# NODE_MCU_EXTEND_Project.net
KiCad netlist of a schematic drawn in Altium Designer
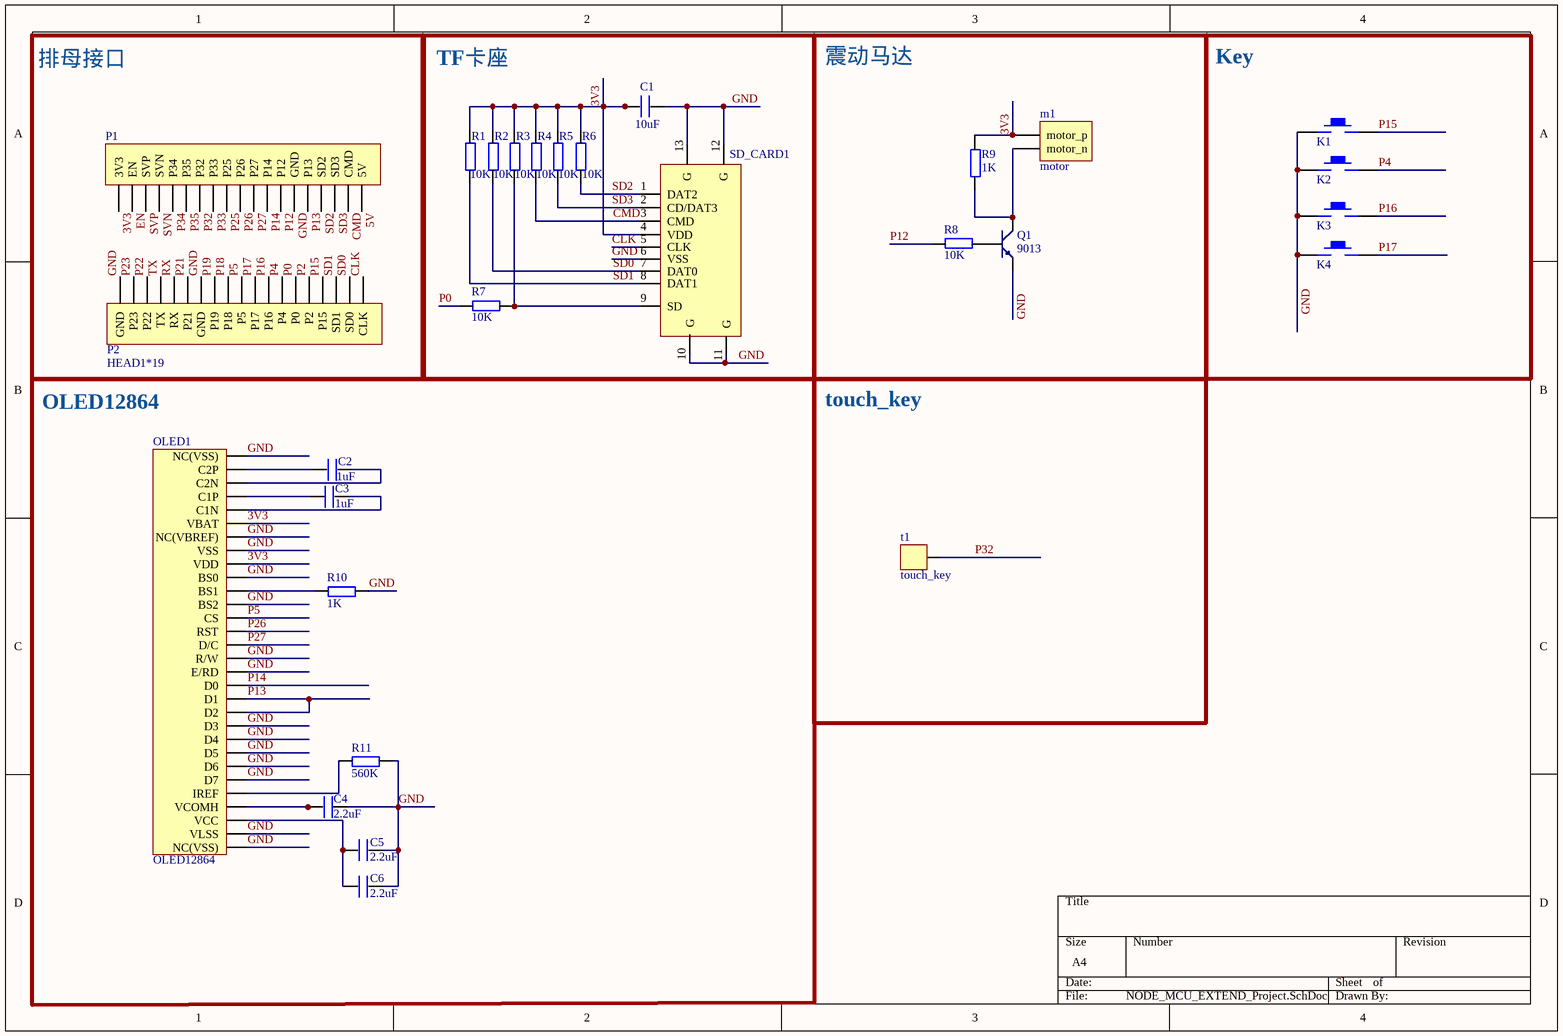
[diagram p0: NODE_MCU_EXTEND_Project.SchDoc]

(export (version "E")
  (design (tool "Eeschema 10.0.6"))
  (components
    (comp (ref "C1")
      (value "10uF")
      (footprint "0603P - duplicate")
      (libsource (lib "altium-import") (part "root_0_C_"))
    )
    (comp (ref "C2")
      (value "1uF")
      (footprint "0603P - duplicate")
      (libsource (lib "altium-import") (part "root_0_C_"))
    )
    (comp (ref "C3")
      (value "1uF")
      (footprint "0603P - duplicate")
      (libsource (lib "altium-import") (part "root_0_C_"))
    )
    (comp (ref "C4")
      (value "2.2uF")
      (footprint "0603P - duplicate")
      (libsource (lib "altium-import") (part "root_0_C_"))
    )
    (comp (ref "C5")
      (value "2.2uF")
      (footprint "0603P - duplicate")
      (libsource (lib "altium-import") (part "root_0_C_"))
    )
    (comp (ref "C6")
      (value "2.2uF")
      (footprint "0603P - duplicate")
      (libsource (lib "altium-import") (part "root_0_C_"))
    )
    (comp (ref "K1")
      (value "KEY_M")
      (footprint "KEY")
      (libsource (lib "NODE_MCU_EXTEND_Project") (part "KEY_M"))
    )
    (comp (ref "K2")
      (value "KEY_M")
      (footprint "KEY")
      (libsource (lib "NODE_MCU_EXTEND_Project") (part "KEY_M"))
    )
    (comp (ref "K3")
      (value "KEY_M")
      (footprint "KEY")
      (libsource (lib "NODE_MCU_EXTEND_Project") (part "KEY_M"))
    )
    (comp (ref "K4")
      (value "KEY_M")
      (footprint "KEY")
      (libsource (lib "NODE_MCU_EXTEND_Project") (part "KEY_M"))
    )
    (comp (ref "m1")
      (value "motor")
      (footprint "motor")
      (fields (field (name "PUBLISHER") "Altium Limited"))
      (libsource (lib "altium-import") (part "root_0_motor_"))
    )
    (comp (ref "OLED1")
      (value "OLED12864")
      (footprint "OLED_1.3")
      (libsource (lib "NODE_MCU_EXTEND_Project") (part "OLED12864"))
    )
    (comp (ref "P1")
      (value "~")
      (footprint "HDR1X19")
      (description "Header, 16-Pin")
      (fields (field (name "PUBLISHER") "Altium Limited"))
      (libsource (lib "altium-import") (part "root_0_Header 19 Up_"))
    )
    (comp (ref "P2")
      (value "HEAD1*19")
      (footprint "HDR1X19")
      (fields (field (name "PUBLISHER") "Altium Limited"))
      (libsource (lib "NODE_MCU_EXTEND_Project") (part "Header 19 Down"))
    )
    (comp (ref "Q1")
      (value "9013")
      (footprint "SOT23-JL")
      (libsource (lib "altium-import") (part "root_0_NPN_"))
    )
    (comp (ref "R1")
      (value "10K")
      (footprint "0603P - duplicate")
      (libsource (lib "NODE_MCU_EXTEND_Project") (part "R"))
    )
    (comp (ref "R2")
      (value "10K")
      (footprint "0603P - duplicate")
      (libsource (lib "NODE_MCU_EXTEND_Project") (part "R"))
    )
    (comp (ref "R3")
      (value "10K")
      (footprint "0603P - duplicate")
      (libsource (lib "NODE_MCU_EXTEND_Project") (part "R"))
    )
    (comp (ref "R4")
      (value "10K")
      (footprint "0603P - duplicate")
      (libsource (lib "NODE_MCU_EXTEND_Project") (part "R"))
    )
    (comp (ref "R5")
      (value "10K")
      (footprint "0603P - duplicate")
      (libsource (lib "NODE_MCU_EXTEND_Project") (part "R"))
    )
    (comp (ref "R6")
      (value "10K")
      (footprint "0603P - duplicate")
      (libsource (lib "NODE_MCU_EXTEND_Project") (part "R"))
    )
    (comp (ref "R7")
      (value "10K")
      (footprint "0603P - duplicate")
      (libsource (lib "NODE_MCU_EXTEND_Project") (part "R"))
    )
    (comp (ref "R8")
      (value "10K")
      (footprint "0603P - duplicate")
      (libsource (lib "NODE_MCU_EXTEND_Project") (part "R"))
    )
    (comp (ref "R9")
      (value "1K")
      (footprint "0603P - duplicate")
      (libsource (lib "NODE_MCU_EXTEND_Project") (part "R"))
    )
    (comp (ref "R10")
      (value "1K")
      (footprint "0603P - duplicate")
      (libsource (lib "NODE_MCU_EXTEND_Project") (part "R"))
    )
    (comp (ref "R11")
      (value "560K")
      (footprint "0603P - duplicate")
      (libsource (lib "NODE_MCU_EXTEND_Project") (part "R"))
    )
    (comp (ref "SD_CARD1")
      (value "~")
      (footprint "CON-TFCARD/AUTO-EJECT")
      (libsource (lib "altium-import") (part "root_0_sd card_"))
    )
    (comp (ref "t1")
      (value "touch_key")
      (footprint "touch_key")
      (libsource (lib "NODE_MCU_EXTEND_Project") (part "touch_key"))
    )
  )
  (nets
    (net (code "1") (name "/3V3") (class "Default")
      (node (ref "C1") (pin "1") (pintype "passive"))
      (node (ref "OLED1") (pin "6") (pinfunction "VBAT_6") (pintype "passive"))
      (node (ref "OLED1") (pin "9") (pinfunction "VDD_9") (pintype "passive"))
      (node (ref "P1") (pin "1") (pinfunction "3V3_1") (pintype "passive"))
      (node (ref "R1") (pin "2") (pintype "passive"))
      (node (ref "R2") (pin "2") (pintype "passive"))
      (node (ref "R3") (pin "2") (pintype "passive"))
      (node (ref "R4") (pin "2") (pintype "passive"))
      (node (ref "R5") (pin "2") (pintype "passive"))
      (node (ref "R6") (pin "2") (pintype "passive"))
      (node (ref "R9") (pin "2") (pintype "passive"))
      (node (ref "SD_CARD1") (pin "4") (pinfunction "VDD_4") (pintype "passive"))
      (node (ref "m1") (pin "1") (pinfunction "motor_p_1") (pintype "passive"))
    )
    (net (code "2") (name "/5V") (class "Default")
      (node (ref "P1") (pin "19") (pinfunction "5V_19") (pintype "passive"))
    )
    (net (code "3") (name "/CLK") (class "Default")
      (node (ref "P2") (pin "19") (pinfunction "CLK_19") (pintype "passive"))
      (node (ref "SD_CARD1") (pin "5") (pinfunction "CLK_5") (pintype "passive"))
    )
    (net (code "4") (name "/CMD") (class "Default")
      (node (ref "P1") (pin "18") (pinfunction "CMD_18") (pintype "passive"))
      (node (ref "R4") (pin "1") (pintype "passive"))
      (node (ref "SD_CARD1") (pin "3") (pinfunction "CMD_3") (pintype "passive"))
    )
    (net (code "5") (name "/EN") (class "Default")
      (node (ref "P1") (pin "2") (pinfunction "EN_2") (pintype "passive"))
    )
    (net (code "6") (name "/GND") (class "Default")
      (node (ref "C1") (pin "2") (pintype "passive"))
      (node (ref "C4") (pin "2") (pintype "passive"))
      (node (ref "C5") (pin "2") (pintype "passive"))
      (node (ref "C6") (pin "2") (pintype "passive"))
      (node (ref "K1") (pin "1") (pinfunction "1_1") (pintype "passive"))
      (node (ref "K2") (pin "1") (pinfunction "1_1") (pintype "passive"))
      (node (ref "K3") (pin "1") (pinfunction "1_1") (pintype "passive"))
      (node (ref "K4") (pin "1") (pinfunction "1_1") (pintype "passive"))
      (node (ref "OLED1") (pin "1") (pinfunction "NC(VSS)_1") (pintype "passive"))
      (node (ref "OLED1") (pin "10") (pinfunction "BS0_10") (pintype "passive"))
      (node (ref "OLED1") (pin "12") (pinfunction "BS2_12") (pintype "passive"))
      (node (ref "OLED1") (pin "16") (pinfunction "R/W_16") (pintype "passive"))
      (node (ref "OLED1") (pin "17") (pinfunction "E/RD_17") (pintype "passive"))
      (node (ref "OLED1") (pin "21") (pinfunction "D3_21") (pintype "passive"))
      (node (ref "OLED1") (pin "22") (pinfunction "D4_22") (pintype "passive"))
      (node (ref "OLED1") (pin "23") (pinfunction "D5_23") (pintype "passive"))
      (node (ref "OLED1") (pin "24") (pinfunction "D6_24") (pintype "passive"))
      (node (ref "OLED1") (pin "25") (pinfunction "D7_25") (pintype "passive"))
      (node (ref "OLED1") (pin "29") (pinfunction "VLSS_29") (pintype "passive"))
      (node (ref "OLED1") (pin "30") (pinfunction "NC(VSS)_30") (pintype "passive"))
      (node (ref "OLED1") (pin "7") (pinfunction "NC(VBREF)_7") (pintype "passive"))
      (node (ref "OLED1") (pin "8") (pinfunction "VSS_8") (pintype "passive"))
      (node (ref "P1") (pin "14") (pinfunction "GND_14") (pintype "passive"))
      (node (ref "P2") (pin "1") (pinfunction "GND_1") (pintype "passive"))
      (node (ref "P2") (pin "7") (pinfunction "GND_7") (pintype "passive"))
      (node (ref "Q1") (pin "2") (pinfunction "E_2") (pintype "passive"))
      (node (ref "R10") (pin "2") (pintype "passive"))
      (node (ref "R11") (pin "2") (pintype "passive"))
      (node (ref "SD_CARD1") (pin "10") (pinfunction "G_10") (pintype "passive"))
      (node (ref "SD_CARD1") (pin "11") (pinfunction "G_11") (pintype "passive"))
      (node (ref "SD_CARD1") (pin "12") (pinfunction "G_12") (pintype "passive"))
      (node (ref "SD_CARD1") (pin "13") (pinfunction "G_13") (pintype "passive"))
      (node (ref "SD_CARD1") (pin "6") (pinfunction "VSS_6") (pintype "passive"))
    )
    (net (code "7") (name "/P0") (class "Default")
      (node (ref "P2") (pin "14") (pinfunction "P0_14") (pintype "passive"))
      (node (ref "R7") (pin "2") (pintype "passive"))
    )
    (net (code "8") (name "/P2") (class "Default")
      (node (ref "P2") (pin "15") (pinfunction "P2_15") (pintype "passive"))
    )
    (net (code "9") (name "/P4") (class "Default")
      (node (ref "K2") (pin "2") (pinfunction "2_2") (pintype "passive"))
      (node (ref "P2") (pin "13") (pinfunction "P4_13") (pintype "passive"))
    )
    (net (code "10") (name "/P5") (class "Default")
      (node (ref "OLED1") (pin "13") (pinfunction "CS_13") (pintype "passive"))
      (node (ref "P2") (pin "10") (pinfunction "P5_10") (pintype "passive"))
    )
    (net (code "11") (name "/P12") (class "Default")
      (node (ref "P1") (pin "13") (pinfunction "P12_13") (pintype "passive"))
      (node (ref "R8") (pin "2") (pintype "passive"))
    )
    (net (code "12") (name "/P13") (class "Default")
      (node (ref "OLED1") (pin "19") (pinfunction "D1_19") (pintype "passive"))
      (node (ref "OLED1") (pin "20") (pinfunction "D2_20") (pintype "passive"))
      (node (ref "P1") (pin "15") (pinfunction "P13_15") (pintype "passive"))
    )
    (net (code "13") (name "/P14") (class "Default")
      (node (ref "OLED1") (pin "18") (pinfunction "D0_18") (pintype "passive"))
      (node (ref "P1") (pin "12") (pinfunction "P14_12") (pintype "passive"))
    )
    (net (code "14") (name "/P15") (class "Default")
      (node (ref "K1") (pin "2") (pinfunction "2_2") (pintype "passive"))
      (node (ref "P2") (pin "16") (pinfunction "P15_16") (pintype "passive"))
    )
    (net (code "15") (name "/P16") (class "Default")
      (node (ref "K3") (pin "2") (pinfunction "2_2") (pintype "passive"))
      (node (ref "P2") (pin "12") (pinfunction "P16_12") (pintype "passive"))
    )
    (net (code "16") (name "/P17") (class "Default")
      (node (ref "K4") (pin "2") (pinfunction "2_2") (pintype "passive"))
      (node (ref "P2") (pin "11") (pinfunction "P17_11") (pintype "passive"))
    )
    (net (code "17") (name "/P18") (class "Default")
      (node (ref "P2") (pin "9") (pinfunction "P18_9") (pintype "passive"))
    )
    (net (code "18") (name "/P19") (class "Default")
      (node (ref "P2") (pin "8") (pinfunction "P19_8") (pintype "passive"))
    )
    (net (code "19") (name "/P21") (class "Default")
      (node (ref "P2") (pin "6") (pinfunction "P21_6") (pintype "passive"))
    )
    (net (code "20") (name "/P22") (class "Default")
      (node (ref "P2") (pin "3") (pinfunction "P22_3") (pintype "passive"))
    )
    (net (code "21") (name "/P23") (class "Default")
      (node (ref "P2") (pin "2") (pinfunction "P23_2") (pintype "passive"))
    )
    (net (code "22") (name "/P25") (class "Default")
      (node (ref "P1") (pin "9") (pinfunction "P25_9") (pintype "passive"))
    )
    (net (code "23") (name "/P26") (class "Default")
      (node (ref "OLED1") (pin "14") (pinfunction "RST_14") (pintype "passive"))
      (node (ref "P1") (pin "10") (pinfunction "P26_10") (pintype "passive"))
    )
    (net (code "24") (name "/P27") (class "Default")
      (node (ref "OLED1") (pin "15") (pinfunction "D/C_15") (pintype "passive"))
      (node (ref "P1") (pin "11") (pinfunction "P27_11") (pintype "passive"))
    )
    (net (code "25") (name "/P32") (class "Default")
      (node (ref "P1") (pin "7") (pinfunction "P32_7") (pintype "passive"))
      (node (ref "t1") (pin "1") (pintype "passive"))
    )
    (net (code "26") (name "/P33") (class "Default")
      (node (ref "P1") (pin "8") (pinfunction "P33_8") (pintype "passive"))
    )
    (net (code "27") (name "/P34") (class "Default")
      (node (ref "P1") (pin "5") (pinfunction "P34_5") (pintype "passive"))
    )
    (net (code "28") (name "/P35") (class "Default")
      (node (ref "P1") (pin "6") (pinfunction "P35_6") (pintype "passive"))
    )
    (net (code "29") (name "/RX") (class "Default")
      (node (ref "P2") (pin "5") (pinfunction "RX_5") (pintype "passive"))
    )
    (net (code "30") (name "/SD0") (class "Default")
      (node (ref "P2") (pin "18") (pinfunction "SD0_18") (pintype "passive"))
      (node (ref "R2") (pin "1") (pintype "passive"))
      (node (ref "SD_CARD1") (pin "7") (pinfunction "DAT0_7") (pintype "passive"))
    )
    (net (code "31") (name "/SD1") (class "Default")
      (node (ref "P2") (pin "17") (pinfunction "SD1_17") (pintype "passive"))
      (node (ref "R1") (pin "1") (pintype "passive"))
      (node (ref "SD_CARD1") (pin "8") (pinfunction "DAT1_8") (pintype "passive"))
    )
    (net (code "32") (name "/SD2") (class "Default")
      (node (ref "P1") (pin "16") (pinfunction "SD2_16") (pintype "passive"))
      (node (ref "R6") (pin "1") (pintype "passive"))
      (node (ref "SD_CARD1") (pin "1") (pinfunction "DAT2_1") (pintype "passive"))
    )
    (net (code "33") (name "/SD3") (class "Default")
      (node (ref "P1") (pin "17") (pinfunction "SD3_17") (pintype "passive"))
      (node (ref "R5") (pin "1") (pintype "passive"))
      (node (ref "SD_CARD1") (pin "2") (pinfunction "CD/DAT3_2") (pintype "passive"))
    )
    (net (code "34") (name "/SVN") (class "Default")
      (node (ref "P1") (pin "4") (pinfunction "SVN_4") (pintype "passive"))
    )
    (net (code "35") (name "/SVP") (class "Default")
      (node (ref "P1") (pin "3") (pinfunction "SVP_3") (pintype "passive"))
    )
    (net (code "36") (name "/TX") (class "Default")
      (node (ref "P2") (pin "4") (pinfunction "TX_4") (pintype "passive"))
    )
    (net (code "37") (name "Net-(OLED1-BS1)") (class "Default")
      (node (ref "OLED1") (pin "11") (pinfunction "BS1_11") (pintype "passive"))
      (node (ref "R10") (pin "1") (pintype "passive"))
    )
    (net (code "38") (name "Net-(OLED1-C1N)") (class "Default")
      (node (ref "C3") (pin "2") (pintype "passive"))
      (node (ref "OLED1") (pin "5") (pinfunction "C1N_5") (pintype "passive"))
    )
    (net (code "39") (name "Net-(OLED1-C1P)") (class "Default")
      (node (ref "C3") (pin "1") (pintype "passive"))
      (node (ref "OLED1") (pin "4") (pinfunction "C1P_4") (pintype "passive"))
    )
    (net (code "40") (name "Net-(OLED1-C2N)") (class "Default")
      (node (ref "C2") (pin "2") (pintype "passive"))
      (node (ref "OLED1") (pin "3") (pinfunction "C2N_3") (pintype "passive"))
    )
    (net (code "41") (name "Net-(OLED1-C2P)") (class "Default")
      (node (ref "C2") (pin "1") (pintype "passive"))
      (node (ref "OLED1") (pin "2") (pinfunction "C2P_2") (pintype "passive"))
    )
    (net (code "42") (name "Net-(OLED1-IREF)") (class "Default")
      (node (ref "OLED1") (pin "26") (pinfunction "IREF_26") (pintype "passive"))
      (node (ref "R11") (pin "1") (pintype "passive"))
    )
    (net (code "43") (name "Net-(OLED1-VCC)") (class "Default")
      (node (ref "C5") (pin "1") (pintype "passive"))
      (node (ref "C6") (pin "1") (pintype "passive"))
      (node (ref "OLED1") (pin "28") (pinfunction "VCC_28") (pintype "passive"))
    )
    (net (code "44") (name "Net-(OLED1-VCOMH)") (class "Default")
      (node (ref "C4") (pin "1") (pintype "passive"))
      (node (ref "OLED1") (pin "27") (pinfunction "VCOMH_27") (pintype "passive"))
    )
    (net (code "45") (name "Net-(Q1-B)") (class "Default")
      (node (ref "Q1") (pin "1") (pinfunction "B_1") (pintype "passive"))
      (node (ref "R8") (pin "1") (pintype "passive"))
    )
    (net (code "46") (name "Net-(Q1-C)") (class "Default")
      (node (ref "Q1") (pin "3") (pinfunction "C_3") (pintype "passive"))
      (node (ref "R9") (pin "1") (pintype "passive"))
      (node (ref "m1") (pin "2") (pinfunction "motor_n_2") (pintype "passive"))
    )
    (net (code "47") (name "Net-(SD_CARD1-SD)") (class "Default")
      (node (ref "R3") (pin "1") (pintype "passive"))
      (node (ref "R7") (pin "1") (pintype "passive"))
      (node (ref "SD_CARD1") (pin "9") (pinfunction "SD_9") (pintype "passive"))
    )
  )
)
